# CSI2-IXORA_Rev01.net
KiCad netlist of a schematic drawn in Altium Designer
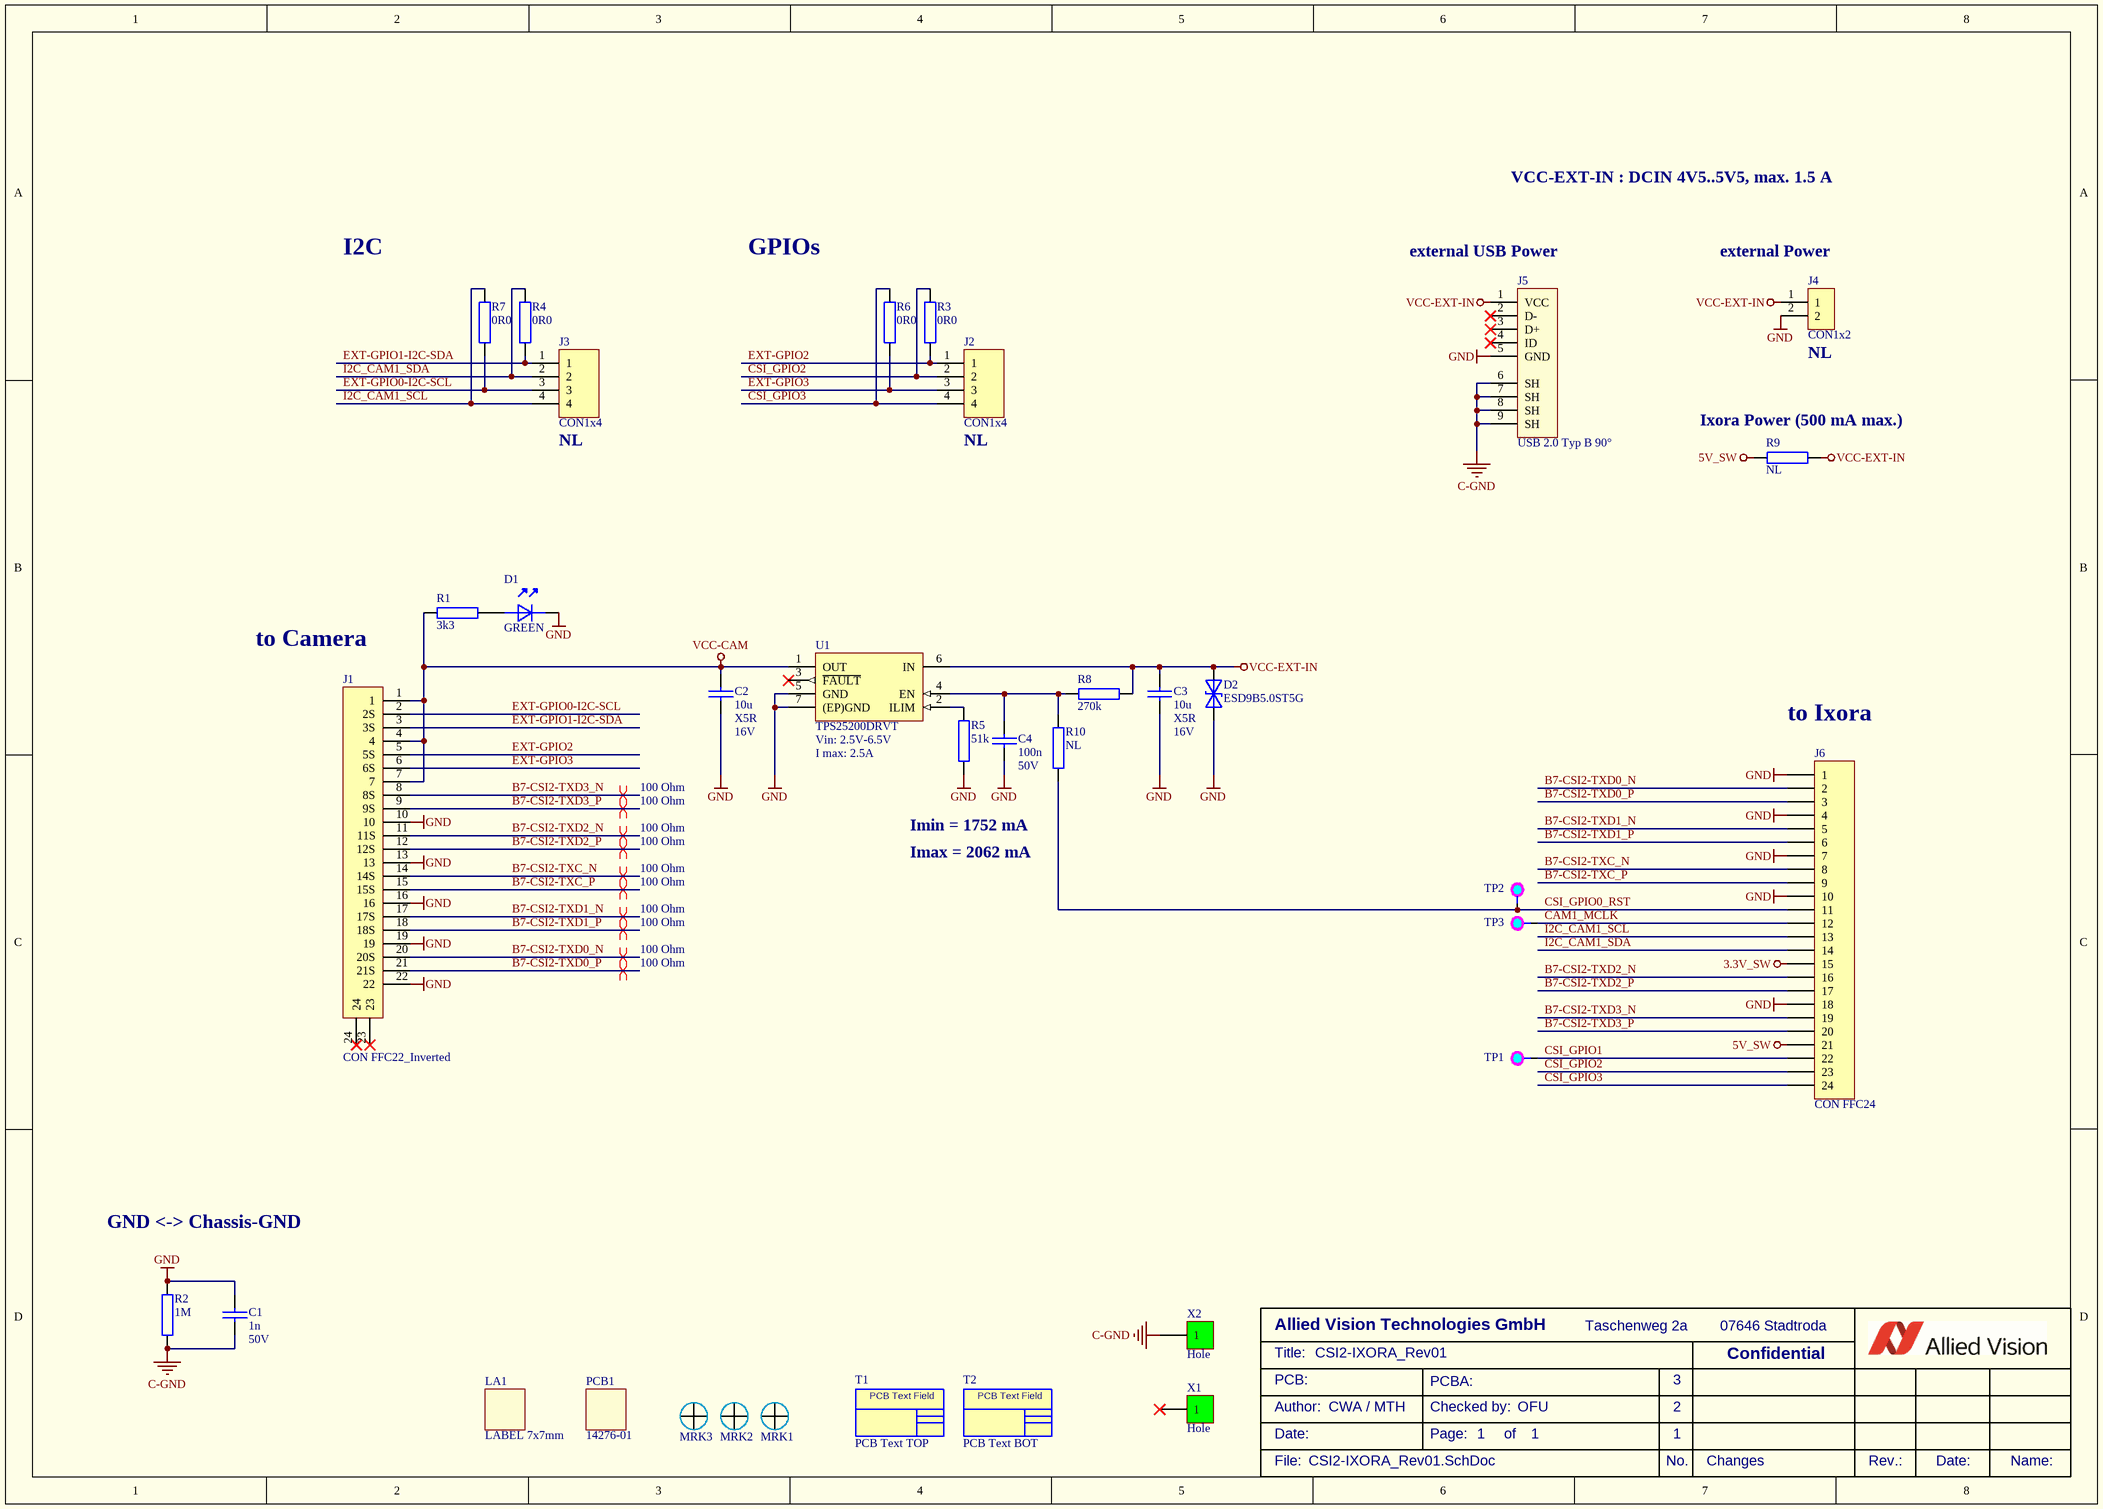
[diagram p0: CSI2-IXORA_Rev01.SchDoc]

(export (version "E")
  (design (tool "Eeschema 10.0.6"))
  (components
    (comp (ref "C1")
      (value "1n")
      (footprint "C-0603_1.0")
      (description "Capacitor Ceramic SMD/0603/50V/X7R/10%")
      (fields
        (field (name "KHK PART NUMBER") "K8340038")
        (field (name "MANUFACTURER") "several")
        (field (name "VOLTAGE") "50V")
      )
      (libsource (lib "AVT_KHK_Lib") (part "C 1N 50V X7R 0603"))
    )
    (comp (ref "C2")
      (value "10u")
      (footprint "C-0805_1.4")
      (description "Capacitor Ceramic SMD/0805/16V/X5R/10%")
      (fields
        (field (name "KHK PART NUMBER") "K8340151")
        (field (name "MANUFACTURER") "several")
        (field (name "DIELECTRIC") "X5R")
        (field (name "VOLTAGE") "16V")
      )
      (libsource (lib "AVT_KHK_Lib") (part "C 10U 16V X5R 0805"))
    )
    (comp (ref "C3")
      (value "10u")
      (footprint "C-0805_1.4")
      (description "Capacitor Ceramic SMD/0805/16V/X5R/10%")
      (fields
        (field (name "KHK PART NUMBER") "K8340151")
        (field (name "MANUFACTURER") "several")
        (field (name "DIELECTRIC") "X5R")
        (field (name "VOLTAGE") "16V")
      )
      (libsource (lib "AVT_KHK_Lib") (part "C 10U 16V X5R 0805"))
    )
    (comp (ref "C4")
      (value "100n")
      (footprint "C-0603_1.0")
      (description "Capacitor Ceramic SMD/0603/50V/X7R/10%")
      (fields
        (field (name "KHK PART NUMBER") "K8340023")
        (field (name "MANUFACTURER") "several")
        (field (name "VOLTAGE") "50V")
      )
      (libsource (lib "AVT_KHK_Lib") (part "C 100N 50V X7R 0603"))
    )
    (comp (ref "D1")
      (value "GREEN")
      (footprint "D-0603-LED")
      (description "Chip LED green 430mcd")
      (fields (field (name "KHK PART NUMBER") "8172") (field (name "MANUFACTURER") "Würth"))
      (libsource (lib "AVT_KHK_Lib") (part "D LED 0603 green"))
    )
    (comp (ref "D2")
      (value "ESD9B5.0ST5G")
      (footprint "D-SOD923")
      (description "DIODE TVS; 400W; 5.8-7.8V; BIDIRECT")
      (fields (field (name "KHK PART NUMBER") "7250") (field (name "MANUFACTURER") "ON Semiconductor"))
      (libsource (lib "AVT_KHK_Lib") (part "D ESD9B5.0ST5G"))
    )
    (comp (ref "J1")
      (value "CON FFC22_Inverted")
      (footprint "J-FH55-22S-0.5SH - Inverted Pins")
      (description "FFC Connector 0.5mm shielded")
      (fields
        (field (name "KHK PART NUMBER") "10357")
        (field (name "MANUFACTURER PART NUMBER") "FH55-22S-0.5SH")
      )
      (libsource (lib "AVT_KHK_Lib") (part "CON FFC22_FH55-22S-0.5SH_Inverted"))
    )
    (comp (ref "J2")
      (value "CON1x4")
      (footprint "CON 1x4 RM2.54")
      (description "Stiftleiste; 1x4; 2.54mm; gerade")
      (fields (field (name "MANUFACTURER") "Harwin") (field (name "MANUFACTURER PART NUMBER") "M20-999 0445"))
      (libsource (lib "AVT_KHK_Lib") (part "CON 1x4 2.54"))
    )
    (comp (ref "J3")
      (value "CON1x4")
      (footprint "CON 1x4 RM2.54")
      (description "Stiftleiste; 1x4; 2.54mm; gerade")
      (fields (field (name "MANUFACTURER") "Harwin") (field (name "MANUFACTURER PART NUMBER") "M20-999 0445"))
      (libsource (lib "AVT_KHK_Lib") (part "CON 1x4 2.54"))
    )
    (comp (ref "J4")
      (value "CON1x2")
      (footprint "CON 1x2 RM2.54")
      (description "Stiftleiste; 1x2; 2.54mm; gerade")
      (fields
        (field (name "MANUFACTURER") "fischer elektronik")
        (field (name "MANUFACTURER PART NUMBER") "SL 11 124 2 G")
      )
      (libsource (lib "AVT_KHK_Lib") (part "CON 1x2 2.54"))
    )
    (comp (ref "J5")
      (value "USB 2.0 Typ B 90°")
      (footprint "J-629105150521")
      (description "Micro USB 2.0 Typ B 90°")
      (fields (field (name "KHK PART NUMBER") "14360") (field (name "MANUFACTURER") "WE"))
      (libsource (lib "Connector") (part "CON USB 2.0 Typ B 90°"))
    )
    (comp (ref "J6")
      (value "CON FFC24")
      (footprint "J-687124182122")
      (description "FFC Connector 0.5mm")
      (fields
        (field (name "KHK PART NUMBER") "14361")
        (field (name "MANUFACTURER PART NUMBER") "687124182122")
      )
      (libsource (lib "AVT_KHK_Lib") (part "CON FFC24_WE_687124182122"))
    )
    (comp (ref "LA1")
      (value "LABEL 7x7mm")
      (footprint "PCB LABEL 7x7")
      (fields (field (name "MANUFACTURER") "several"))
      (libsource (lib "AVT_KHK_Lib") (part "PCB LABEL 7x7"))
    )
    (comp (ref "MRK1")
      (value "Marker Single Layer")
      (footprint "PCB_Marker_Pad_top")
      (description "Position Marker for PCBs")
      (libsource (lib "AVT_KHK_Lib") (part "PCB Marker Pad Single Layer"))
    )
    (comp (ref "MRK2")
      (value "Marker Single Layer")
      (footprint "PCB_Marker_Pad_top")
      (description "Position Marker for PCBs")
      (libsource (lib "AVT_KHK_Lib") (part "PCB Marker Pad Single Layer"))
    )
    (comp (ref "MRK3")
      (value "Marker Single Layer")
      (footprint "PCB_Marker_Pad_top")
      (description "Position Marker for PCBs")
      (libsource (lib "AVT_KHK_Lib") (part "PCB Marker Pad Single Layer"))
    )
    (comp (ref "PCB1")
      (value "14276-01")
      (description "PCB ML04")
      (fields (field (name "MANUFACTURER") "several"))
      (libsource (lib "AVT_KHK_Lib") (part "PCB"))
    )
    (comp (ref "R1")
      (value "3k3")
      (footprint "R-0603_0.6")
      (description "Standard Resistor SMD/0603/1%/100mW/TK100")
      (fields (field (name "KHK PART NUMBER") "K8250070") (field (name "MANUFACTURER") "several"))
      (libsource (lib "AVT_KHK_Lib") (part "R 3K3 1% 0603"))
    )
    (comp (ref "R2")
      (value "1M")
      (footprint "R-0603_0.6")
      (description "Standard Resistor SMD/0603/1%/100mW/TK100")
      (fields (field (name "KHK PART NUMBER") "K8250058") (field (name "MANUFACTURER") "several"))
      (libsource (lib "AVT_KHK_Lib") (part "R 1MEG 1% 0603"))
    )
    (comp (ref "R3")
      (value "0R0")
      (footprint "R-0603_0.6")
      (description "Standard Resistor SMD/0603/1%/100mW/TK200")
      (fields (field (name "KHK PART NUMBER") "K8250041") (field (name "MANUFACTURER") "several"))
      (libsource (lib "AVT_KHK_Lib") (part "R 0R0 1% 0603"))
    )
    (comp (ref "R4")
      (value "0R0")
      (footprint "R-0603_0.6")
      (description "Standard Resistor SMD/0603/1%/100mW/TK100")
      (fields (field (name "KHK PART NUMBER") "K8250041") (field (name "MANUFACTURER") "several"))
      (libsource (lib "AVT_KHK_Lib") (part "R 0R0 1% 0603"))
    )
    (comp (ref "R5")
      (value "51k")
      (footprint "R-0603_0.6")
      (description "Standard Resistor SMD/0603/1%/100mW/TK100")
      (fields (field (name "KHK PART NUMBER") "K8250156") (field (name "MANUFACTURER") "several"))
      (libsource (lib "AVT_KHK_Lib") (part "R 51K 1% 0603"))
    )
    (comp (ref "R6")
      (value "0R0")
      (footprint "R-0603_0.6")
      (description "Standard Resistor SMD/0603/1%/100mW/TK200")
      (fields (field (name "KHK PART NUMBER") "K8250041") (field (name "MANUFACTURER") "several"))
      (libsource (lib "AVT_KHK_Lib") (part "R 0R0 1% 0603"))
    )
    (comp (ref "R7")
      (value "0R0")
      (footprint "R-0603_0.6")
      (description "Standard Resistor SMD/0603/1%/100mW/TK100")
      (fields (field (name "KHK PART NUMBER") "K8250041") (field (name "MANUFACTURER") "several"))
      (libsource (lib "AVT_KHK_Lib") (part "R 0R0 1% 0603"))
    )
    (comp (ref "R8")
      (value "270k")
      (footprint "R-0603_0.6")
      (description "Standard Resistor SMD/0603/1%/100mW/TK100")
      (fields (field (name "KHK PART NUMBER") "K8250170") (field (name "MANUFACTURER") "several"))
      (libsource (lib "AVT_KHK_Lib") (part "R 270K 1% 0603"))
    )
    (comp (ref "R9")
      (value "NL")
      (footprint "R-0603_0.6")
      (description "Standard Resistor SMD/0603/1%/100mW/TK200")
      (fields (field (name "TOLERANCE") "1%"))
      (libsource (lib "AVT_KHK_Lib") (part "R X 0603"))
    )
    (comp (ref "R10")
      (value "NL")
      (footprint "R-0603_0.6")
      (description "Standard Resistor SMD/0603/1%/100mW/TK200")
      (fields (field (name "TOLERANCE") "1%"))
      (libsource (lib "AVT_KHK_Lib") (part "R X 0603"))
    )
    (comp (ref "T1")
      (value "PCB Text TOP")
      (footprint "PCB TEXTFIELD TOP 2")
      (description "PCB Textfield TOP")
      (libsource (lib "AVT_KHK_Lib") (part "PCB TEXT FIELD TOP"))
    )
    (comp (ref "T2")
      (value "PCB Text BOT")
      (footprint "PCB TEXTFIELD BOT 2")
      (description "PCB Textfield BOT")
      (libsource (lib "AVT_KHK_Lib") (part "PCB TEXT FIELD BOT"))
    )
    (comp (ref "TP1")
      (value "TP")
      (footprint "TP_16_10")
      (description "Testpoint: Pad=1,6mm; Hole=1,0mm")
      (libsource (lib "AVT_KHK_Lib") (part "TP_16_10"))
    )
    (comp (ref "TP2")
      (value "TP")
      (footprint "TP_16_10")
      (description "Testpoint: Pad=1,6mm; Hole=1,0mm")
      (libsource (lib "AVT_KHK_Lib") (part "TP_16_10"))
    )
    (comp (ref "TP3")
      (value "TP")
      (footprint "TP_16_10")
      (description "Testpoint: Pad=1,6mm; Hole=1,0mm")
      (libsource (lib "AVT_KHK_Lib") (part "TP_16_10"))
    )
    (comp (ref "U1")
      (value "TPS25200DRVT")
      (footprint "IC-DFN06_2.0x2.0x0.8")
      (description "IC/PWR/LOADSW;2V5-6V5;2A5;0R099/6-WDFN/2x2x0.8mm")
      (fields
        (field (name "KHK PART NUMBER") "14277")
        (field (name "MANUFACTURER") "Texas Instruments")
        (field (name "VIN") "2.5V-6.5V")
        (field (name "I MAX") "2.5A")
      )
      (libsource (lib "AVT_KHK_Lib") (part "IC  TPS25200DRVT"))
    )
    (comp (ref "X1")
      (value "Hole")
      (footprint "HOLE-2.6-5.0-DK")
      (description "HOLE M2.5")
      (libsource (lib "AVT_KHK_Lib") (part "PCB HOLE M2.5-5-DK"))
    )
    (comp (ref "X2")
      (value "Hole")
      (footprint "HOLE-2.6-5.0-DK")
      (description "HOLE M2.5")
      (libsource (lib "AVT_KHK_Lib") (part "PCB HOLE M2.5-5-DK"))
    )
  )
  (nets
    (net (code "1") (name "/B7-CSI2-TXC_N") (class "Default")
      (node (ref "J1") (pin "14") (pinfunction "14S_14") (pintype "passive"))
      (node (ref "J6") (pin "8") (pinfunction "8_8") (pintype "passive"))
    )
    (net (code "2") (name "/B7-CSI2-TXC_P") (class "Default")
      (node (ref "J1") (pin "15") (pinfunction "15S_15") (pintype "passive"))
      (node (ref "J6") (pin "9") (pinfunction "9_9") (pintype "passive"))
    )
    (net (code "3") (name "/B7-CSI2-TXD0_N") (class "Default")
      (node (ref "J1") (pin "20") (pinfunction "20S_20") (pintype "passive"))
      (node (ref "J6") (pin "2") (pinfunction "2_2") (pintype "passive"))
    )
    (net (code "4") (name "/B7-CSI2-TXD0_P") (class "Default")
      (node (ref "J1") (pin "21") (pinfunction "21S_21") (pintype "passive"))
      (node (ref "J6") (pin "3") (pinfunction "3_3") (pintype "passive"))
    )
    (net (code "5") (name "/B7-CSI2-TXD1_N") (class "Default")
      (node (ref "J1") (pin "17") (pinfunction "17S_17") (pintype "passive"))
      (node (ref "J6") (pin "5") (pinfunction "5_5") (pintype "passive"))
    )
    (net (code "6") (name "/B7-CSI2-TXD1_P") (class "Default")
      (node (ref "J1") (pin "18") (pinfunction "18S_18") (pintype "passive"))
      (node (ref "J6") (pin "6") (pinfunction "6_6") (pintype "passive"))
    )
    (net (code "7") (name "/B7-CSI2-TXD2_N") (class "Default")
      (node (ref "J1") (pin "11") (pinfunction "11S_11") (pintype "passive"))
      (node (ref "J6") (pin "16") (pinfunction "16_16") (pintype "passive"))
    )
    (net (code "8") (name "/B7-CSI2-TXD2_P") (class "Default")
      (node (ref "J1") (pin "12") (pinfunction "12S_12") (pintype "passive"))
      (node (ref "J6") (pin "17") (pinfunction "17_17") (pintype "passive"))
    )
    (net (code "9") (name "/B7-CSI2-TXD3_N") (class "Default")
      (node (ref "J1") (pin "8") (pinfunction "8S_8") (pintype "passive"))
      (node (ref "J6") (pin "19") (pinfunction "19_19") (pintype "passive"))
    )
    (net (code "10") (name "/B7-CSI2-TXD3_P") (class "Default")
      (node (ref "J1") (pin "9") (pinfunction "9S_9") (pintype "passive"))
      (node (ref "J6") (pin "20") (pinfunction "20_20") (pintype "passive"))
    )
    (net (code "11") (name "/CAM1_MCLK") (class "Default")
      (node (ref "J6") (pin "12") (pinfunction "12_12") (pintype "passive"))
      (node (ref "TP3") (pin "1") (pinfunction "1_1") (pintype "passive"))
    )
    (net (code "12") (name "/CSI_GPIO0_RST") (class "Default")
      (node (ref "J6") (pin "11") (pinfunction "11_11") (pintype "passive"))
      (node (ref "R10") (pin "1") (pinfunction "1_1") (pintype "passive"))
      (node (ref "TP2") (pin "1") (pinfunction "1_1") (pintype "passive"))
    )
    (net (code "13") (name "/CSI_GPIO1") (class "Default")
      (node (ref "J6") (pin "22") (pinfunction "22_22") (pintype "passive"))
      (node (ref "TP1") (pin "1") (pinfunction "1_1") (pintype "passive"))
    )
    (net (code "14") (name "/CSI_GPIO2") (class "Default")
      (node (ref "J2") (pin "2") (pinfunction "2_2") (pintype "passive"))
      (node (ref "J6") (pin "23") (pinfunction "23_23") (pintype "passive"))
      (node (ref "R3") (pin "2") (pinfunction "2_2") (pintype "passive"))
    )
    (net (code "15") (name "/CSI_GPIO3") (class "Default")
      (node (ref "J2") (pin "4") (pinfunction "4_4") (pintype "passive"))
      (node (ref "J6") (pin "24") (pinfunction "24_24") (pintype "passive"))
      (node (ref "R6") (pin "2") (pinfunction "2_2") (pintype "passive"))
    )
    (net (code "16") (name "/EXT-GPIO0-I2C-SCL") (class "Default")
      (node (ref "J1") (pin "2") (pinfunction "2S_2") (pintype "passive"))
      (node (ref "J3") (pin "3") (pinfunction "3_3") (pintype "passive"))
      (node (ref "R7") (pin "1") (pinfunction "1_1") (pintype "passive"))
    )
    (net (code "17") (name "/EXT-GPIO1-I2C-SDA") (class "Default")
      (node (ref "J1") (pin "3") (pinfunction "3S_3") (pintype "passive"))
      (node (ref "J3") (pin "1") (pinfunction "1_1") (pintype "passive"))
      (node (ref "R4") (pin "1") (pinfunction "1_1") (pintype "passive"))
    )
    (net (code "18") (name "/EXT-GPIO2") (class "Default")
      (node (ref "J1") (pin "5") (pinfunction "5S_5") (pintype "passive"))
      (node (ref "J2") (pin "1") (pinfunction "1_1") (pintype "passive"))
      (node (ref "R3") (pin "1") (pinfunction "1_1") (pintype "passive"))
    )
    (net (code "19") (name "/EXT-GPIO3") (class "Default")
      (node (ref "J1") (pin "6") (pinfunction "6S_6") (pintype "passive"))
      (node (ref "J2") (pin "3") (pinfunction "3_3") (pintype "passive"))
      (node (ref "R6") (pin "1") (pinfunction "1_1") (pintype "passive"))
    )
    (net (code "20") (name "/I2C_CAM1_SCL") (class "Default")
      (node (ref "J3") (pin "4") (pinfunction "4_4") (pintype "passive"))
      (node (ref "J6") (pin "13") (pinfunction "13_13") (pintype "passive"))
      (node (ref "R7") (pin "2") (pinfunction "2_2") (pintype "passive"))
    )
    (net (code "21") (name "/I2C_CAM1_SDA") (class "Default")
      (node (ref "J3") (pin "2") (pinfunction "2_2") (pintype "passive"))
      (node (ref "J6") (pin "14") (pinfunction "14_14") (pintype "passive"))
      (node (ref "R4") (pin "2") (pinfunction "2_2") (pintype "passive"))
    )
    (net (code "22") (name "3.3V_SW") (class "Default")
      (node (ref "J6") (pin "15") (pinfunction "15_15") (pintype "passive"))
    )
    (net (code "23") (name "5V_SW") (class "Default")
      (node (ref "J6") (pin "21") (pinfunction "21_21") (pintype "passive"))
      (node (ref "R9") (pin "2") (pinfunction "2_2") (pintype "passive"))
    )
    (net (code "24") (name "C-GND") (class "Default")
      (node (ref "C1") (pin "2") (pinfunction "2_2") (pintype "passive"))
      (node (ref "J5") (pin "6") (pinfunction "SH_6") (pintype "passive"))
      (node (ref "J5") (pin "7") (pinfunction "SH_7") (pintype "passive"))
      (node (ref "J5") (pin "8") (pinfunction "SH_8") (pintype "passive"))
      (node (ref "J5") (pin "9") (pinfunction "SH_9") (pintype "passive"))
      (node (ref "R2") (pin "1") (pinfunction "1_1") (pintype "passive"))
      (node (ref "X2") (pin "1") (pinfunction "1_1") (pintype "passive"))
    )
    (net (code "25") (name "GND") (class "Default")
      (node (ref "C1") (pin "1") (pinfunction "1_1") (pintype "passive"))
      (node (ref "C2") (pin "2") (pinfunction "2_2") (pintype "passive"))
      (node (ref "C3") (pin "2") (pinfunction "2_2") (pintype "passive"))
      (node (ref "C4") (pin "2") (pinfunction "2_2") (pintype "passive"))
      (node (ref "D1") (pin "K") (pinfunction "2_K") (pintype "passive"))
      (node (ref "D2") (pin "A") (pinfunction "A_A") (pintype "passive"))
      (node (ref "J1") (pin "10") (pinfunction "10_10") (pintype "passive"))
      (node (ref "J1") (pin "13") (pinfunction "13_13") (pintype "passive"))
      (node (ref "J1") (pin "16") (pinfunction "16_16") (pintype "passive"))
      (node (ref "J1") (pin "19") (pinfunction "19_19") (pintype "passive"))
      (node (ref "J1") (pin "22") (pinfunction "22_22") (pintype "passive"))
      (node (ref "J4") (pin "2") (pinfunction "2_2") (pintype "passive"))
      (node (ref "J5") (pin "5") (pinfunction "GND_5") (pintype "passive"))
      (node (ref "J6") (pin "1") (pinfunction "1_1") (pintype "passive"))
      (node (ref "J6") (pin "10") (pinfunction "10_10") (pintype "passive"))
      (node (ref "J6") (pin "18") (pinfunction "18_18") (pintype "passive"))
      (node (ref "J6") (pin "4") (pinfunction "4_4") (pintype "passive"))
      (node (ref "J6") (pin "7") (pinfunction "7_7") (pintype "passive"))
      (node (ref "R2") (pin "2") (pinfunction "2_2") (pintype "passive"))
      (node (ref "R5") (pin "1") (pinfunction "1_1") (pintype "passive"))
      (node (ref "U1") (pin "5") (pinfunction "GND_5") (pintype "power_in"))
      (node (ref "U1") (pin "7") (pinfunction "(EP)GND_7") (pintype "power_in"))
    )
    (net (code "26") (name "Net-(D1-1)") (class "Default")
      (node (ref "D1") (pin "A") (pinfunction "1_A") (pintype "passive"))
      (node (ref "R1") (pin "2") (pinfunction "2_2") (pintype "passive"))
    )
    (net (code "27") (name "Net-(U1-EN)") (class "Default")
      (node (ref "C4") (pin "1") (pinfunction "1_1") (pintype "passive"))
      (node (ref "R10") (pin "2") (pinfunction "2_2") (pintype "passive"))
      (node (ref "R8") (pin "1") (pinfunction "1_1") (pintype "passive"))
      (node (ref "U1") (pin "4") (pinfunction "EN_4") (pintype "input"))
    )
    (net (code "28") (name "Net-(U1-ILIM)") (class "Default")
      (node (ref "R5") (pin "2") (pinfunction "2_2") (pintype "passive"))
      (node (ref "U1") (pin "2") (pinfunction "ILIM_2") (pintype "input"))
    )
    (net (code "29") (name "VCC-CAM") (class "Default")
      (node (ref "C2") (pin "1") (pinfunction "1_1") (pintype "passive"))
      (node (ref "J1") (pin "1") (pinfunction "1_1") (pintype "passive"))
      (node (ref "J1") (pin "4") (pinfunction "4_4") (pintype "passive"))
      (node (ref "J1") (pin "7") (pinfunction "7_7") (pintype "passive"))
      (node (ref "R1") (pin "1") (pinfunction "1_1") (pintype "passive"))
      (node (ref "U1") (pin "1") (pinfunction "OUT_1") (pintype "power_in"))
    )
    (net (code "30") (name "VCC-EXT-IN") (class "Default")
      (node (ref "C3") (pin "1") (pinfunction "1_1") (pintype "passive"))
      (node (ref "D2") (pin "K") (pinfunction "K_K") (pintype "passive"))
      (node (ref "J4") (pin "1") (pinfunction "1_1") (pintype "passive"))
      (node (ref "J5") (pin "1") (pinfunction "VCC_1") (pintype "passive"))
      (node (ref "R8") (pin "2") (pinfunction "2_2") (pintype "passive"))
      (node (ref "R9") (pin "1") (pinfunction "1_1") (pintype "passive"))
      (node (ref "U1") (pin "6") (pinfunction "IN_6") (pintype "power_in"))
    )
    (net (code "31") (name "unconnected-(J1-Pad23)") (class "Default")
      (node (ref "J1") (pin "23") (pinfunction "23_23") (pintype "passive+no_connect"))
    )
    (net (code "32") (name "unconnected-(J1-Pad24)") (class "Default")
      (node (ref "J1") (pin "24") (pinfunction "24_24") (pintype "passive+no_connect"))
    )
    (net (code "33") (name "unconnected-(J5-D+-Pad3)") (class "Default")
      (node (ref "J5") (pin "3") (pinfunction "D+_3") (pintype "passive+no_connect"))
    )
    (net (code "34") (name "unconnected-(J5-D--Pad2)") (class "Default")
      (node (ref "J5") (pin "2") (pinfunction "D-_2") (pintype "passive+no_connect"))
    )
    (net (code "35") (name "unconnected-(J5-ID-Pad4)") (class "Default")
      (node (ref "J5") (pin "4") (pinfunction "ID_4") (pintype "passive+no_connect"))
    )
    (net (code "36") (name "unconnected-(U1-~{FAULT}-Pad3)") (class "Default")
      (node (ref "U1") (pin "3") (pinfunction "~{FAULT}_3") (pintype "output+no_connect"))
    )
    (net (code "37") (name "unconnected-(X1-Pad1)") (class "Default")
      (node (ref "X1") (pin "1") (pinfunction "1_1") (pintype "passive+no_connect"))
    )
  )
)
